# NRF24L01.net
KiCad netlist of a schematic drawn in Altium Designer
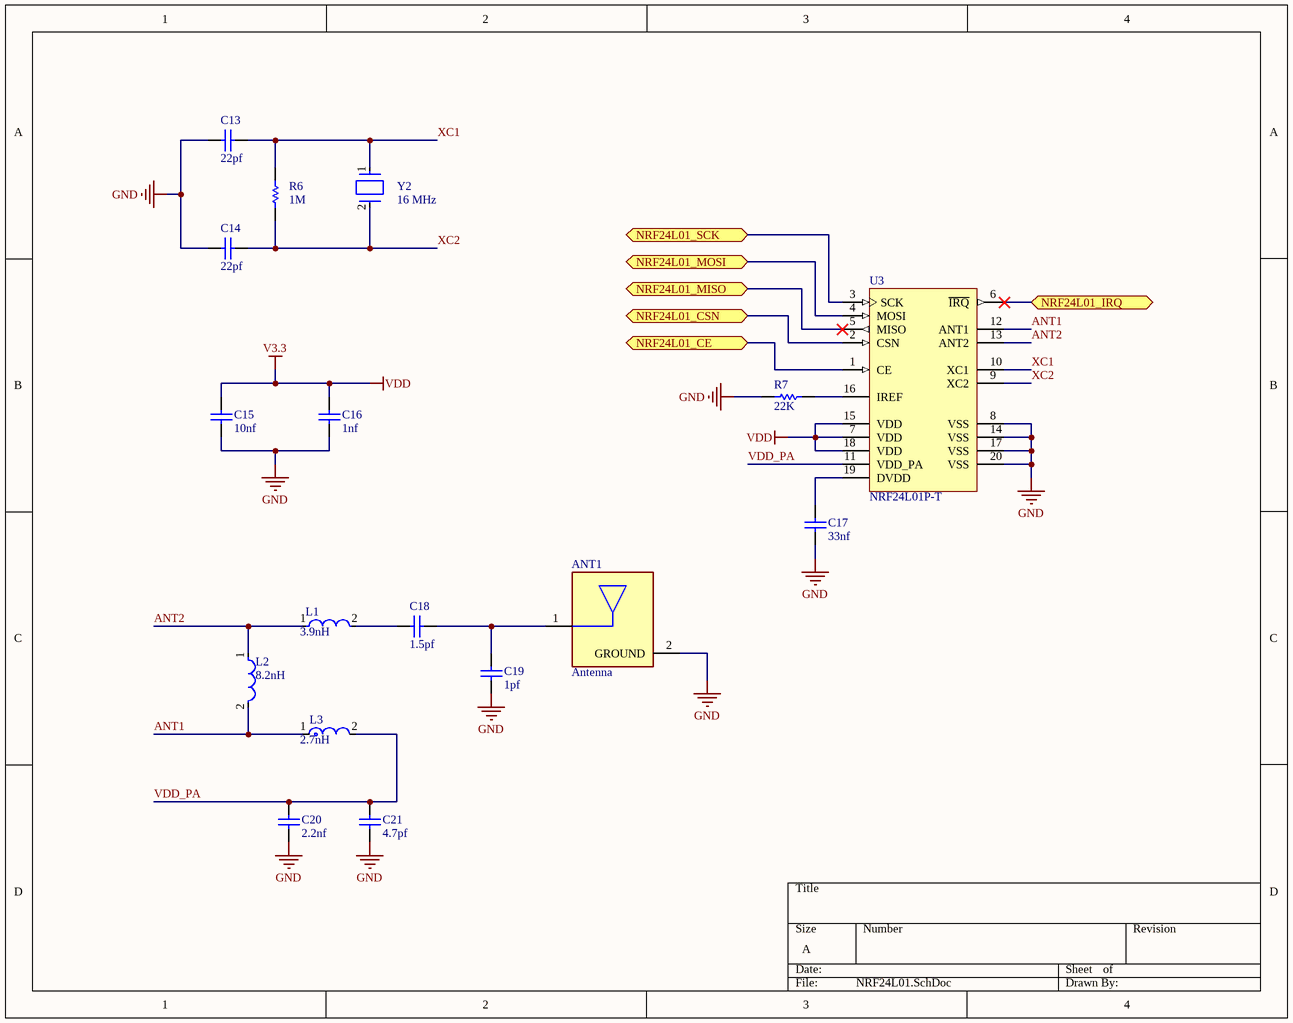
[diagram p0: NRF24L01.SchDoc]

(export (version "E")
  (design (tool "Eeschema 10.0.6"))
  (components
    (comp (ref "ANT1")
      (value "Antenna")
      (footprint "FP-211964-0001-MFG")
      (description "2.4/5GHZ LTCC ANT 3.2X1.6MM")
      (libsource (lib "Altium Content Vault") (part "8e307a9ba41921a4a20067ae005fd5e"))
    )
    (comp (ref "C13")
      (value "22pf")
      (footprint "CAPC1206(3216)190_N")
      (description "CAP 1206")
      (fields (field (name "TOLERANCE") "Â±10%"))
      (libsource (lib "Altium Content Vault") (part "CAP"))
    )
    (comp (ref "C14")
      (value "22pf")
      (footprint "CAPC1206(3216)190_N")
      (description "CAP 1206")
      (fields (field (name "TOLERANCE") "Â±10%"))
      (libsource (lib "Altium Content Vault") (part "CAP"))
    )
    (comp (ref "C15")
      (value "10nf")
      (footprint "CAPC1206(3216)190_N")
      (description "CAP 1206")
      (fields (field (name "TOLERANCE") "Â±10%"))
      (libsource (lib "Altium Content Vault") (part "CAP"))
    )
    (comp (ref "C16")
      (value "1nf")
      (footprint "CAPC1206(3216)190_N")
      (description "CAP 1206")
      (fields (field (name "TOLERANCE") "Â±10%"))
      (libsource (lib "Altium Content Vault") (part "CAP"))
    )
    (comp (ref "C17")
      (value "33nf")
      (footprint "CAPC1206(3216)190_N")
      (description "CAP 1206")
      (fields (field (name "TOLERANCE") "Â±10%"))
      (libsource (lib "Altium Content Vault") (part "CAP"))
    )
    (comp (ref "C18")
      (value "1.5pf")
      (footprint "CAPC1206(3216)190_N")
      (description "CAP 1206")
      (fields (field (name "TOLERANCE") "Â±10%"))
      (libsource (lib "Altium Content Vault") (part "CAP"))
    )
    (comp (ref "C19")
      (value "1pf")
      (footprint "CAPC1206(3216)190_N")
      (description "CAP 1206")
      (fields (field (name "TOLERANCE") "Â±10%"))
      (libsource (lib "Altium Content Vault") (part "CAP"))
    )
    (comp (ref "C20")
      (value "2.2nf")
      (footprint "CAPC1206(3216)190_N")
      (description "CAP 1206")
      (fields (field (name "TOLERANCE") "Â±10%"))
      (libsource (lib "Altium Content Vault") (part "CAP"))
    )
    (comp (ref "C21")
      (value "4.7pf")
      (footprint "CAPC1206(3216)190_N")
      (description "CAP 1206")
      (fields (field (name "TOLERANCE") "Â±10%"))
      (libsource (lib "Altium Content Vault") (part "CAP"))
    )
    (comp (ref "L1")
      (value "LQM21NNR15K10D")
      (footprint "FP-LQM21DN_00-IPC_B")
      (description "Multilayer Type Inductor for General Circuits, 0805 (2012), 0.15μH, 10%, 0.32Ω, 250mA")
      (fields (field (name "INDUCTANCE") "3.9nH") (field (name "TOLERANCE") "10%"))
      (libsource (lib "Altium Content Vault") (part "725321dda6339637d4d059423bc1c3c"))
    )
    (comp (ref "L2")
      (value "LQM21NNR15K10D")
      (footprint "FP-LQM21DN_00-IPC_B")
      (description "Multilayer Type Inductor for General Circuits, 0805 (2012), 0.15μH, 10%, 0.32Ω, 250mA")
      (fields (field (name "INDUCTANCE") "8.2nH") (field (name "TOLERANCE") "10%"))
      (libsource (lib "Altium Content Vault") (part "725321dda6339637d4d059423bc1c3c"))
    )
    (comp (ref "L3")
      (value "LQG18HN2N2S00D")
      (footprint "FP-LQG18HH_00-IPC_A")
      (description "Multilayer type RF Inductor 2.2nH ±0.3nH 0.1Ω 1100mA 0603")
      (fields (field (name "INDUCTANCE") "2.7nH"))
      (libsource (lib "Altium Content Vault") (part "4cc4b267dca4c8e51f7102f422741d8"))
    )
    (comp (ref "R6")
      (value "1M")
      (footprint "RESC3216X70X50NL05T20")
      (fields (field (name "MANUFACTURER") "Panasonic") (field (name "PART NUMBER") "ERJ-8GEY0R00V"))
      (libsource (lib "Altium Content Vault") (part "RES"))
    )
    (comp (ref "R7")
      (value "22K")
      (footprint "RESC3216X70X50NL05T20")
      (fields (field (name "MANUFACTURER") "Panasonic") (field (name "PART NUMBER") "ERJ-8GEY0R00V"))
      (libsource (lib "Altium Content Vault") (part "RES"))
    )
    (comp (ref "U3")
      (value "NRF24L01P-T")
      (footprint "NRSC-QFN-20_L")
      (description "Single Chip Transceiver, 2.4 GHz, 60 mW, 1.9 to 3.6 V, -40 to 85 degC, 20-Pin QFN, RoHS, Tray")
      (fields (field (name "MANUFACTURER") "Nordic Semiconductor"))
      (libsource (lib "Altium Content Vault") (part "NRSC-NRF24L01P-QFN-20"))
    )
    (comp (ref "Y2")
      (value "ABLS-8.000MHZ-B2-T")
      (footprint "FP-ABLS-MFG")
      (description "CRYSTAL 8.0000MHZ 18PF SMD")
      (fields (field (name "OPERATING FREQUENCY") "16 MHz") (field (name "TOLERANCE") "20ppm"))
      (libsource (lib "Altium Content Vault") (part "c23a69dc6c9e2f18f2079038eb95dd1"))
    )
  )
  (nets
    (net (code "1") (name "/ANT1") (class "Default")
      (node (ref "L2") (pin "2") (pinfunction "2_2") (pintype "passive"))
      (node (ref "L3") (pin "1") (pinfunction "1_1") (pintype "passive"))
      (node (ref "U3") (pin "12") (pinfunction "ANT1_12") (pintype "passive"))
    )
    (net (code "2") (name "/ANT2") (class "Default")
      (node (ref "L1") (pin "1") (pinfunction "1_1") (pintype "passive"))
      (node (ref "L2") (pin "1") (pinfunction "1_1") (pintype "passive"))
      (node (ref "U3") (pin "13") (pinfunction "ANT2_13") (pintype "passive"))
    )
    (net (code "3") (name "/NRF24L01_CE") (class "Default")
      (node (ref "U3") (pin "1") (pinfunction "CE_1") (pintype "input"))
    )
    (net (code "4") (name "/NRF24L01_CSN") (class "Default")
      (node (ref "U3") (pin "2") (pinfunction "CSN_2") (pintype "input"))
    )
    (net (code "5") (name "/NRF24L01_IRQ") (class "Default")
      (node (ref "U3") (pin "6") (pinfunction "~{IRQ}_6") (pintype "output+no_connect"))
    )
    (net (code "6") (name "/NRF24L01_MISO") (class "Default")
      (node (ref "U3") (pin "5") (pinfunction "MISO_5") (pintype "output+no_connect"))
    )
    (net (code "7") (name "/NRF24L01_MOSI") (class "Default")
      (node (ref "U3") (pin "4") (pinfunction "MOSI_4") (pintype "input"))
    )
    (net (code "8") (name "/NRF24L01_SCK") (class "Default")
      (node (ref "U3") (pin "3") (pinfunction "SCK_3") (pintype "input"))
    )
    (net (code "9") (name "/VDD_PA") (class "Default")
      (node (ref "C20") (pin "2") (pinfunction "2_2") (pintype "passive"))
      (node (ref "C21") (pin "2") (pinfunction "2_2") (pintype "passive"))
      (node (ref "L3") (pin "2") (pinfunction "2_2") (pintype "passive"))
      (node (ref "U3") (pin "11") (pinfunction "VDD_PA_11") (pintype "power_in"))
    )
    (net (code "10") (name "/XC1") (class "Default")
      (node (ref "C13") (pin "1") (pinfunction "1_1") (pintype "passive"))
      (node (ref "R6") (pin "2") (pinfunction "2_2") (pintype "passive"))
      (node (ref "U3") (pin "10") (pinfunction "XC1_10") (pintype "passive"))
      (node (ref "Y2") (pin "1") (pinfunction "1_1") (pintype "passive"))
    )
    (net (code "11") (name "/XC2") (class "Default")
      (node (ref "C14") (pin "1") (pinfunction "1_1") (pintype "passive"))
      (node (ref "R6") (pin "1") (pinfunction "1_1") (pintype "passive"))
      (node (ref "U3") (pin "9") (pinfunction "XC2_9") (pintype "passive"))
      (node (ref "Y2") (pin "2") (pinfunction "2_2") (pintype "passive"))
    )
    (net (code "12") (name "GND") (class "Default")
      (node (ref "ANT1") (pin "2") (pinfunction "GROUND_2") (pintype "power_in"))
      (node (ref "C13") (pin "2") (pinfunction "2_2") (pintype "passive"))
      (node (ref "C14") (pin "2") (pinfunction "2_2") (pintype "passive"))
      (node (ref "C15") (pin "2") (pinfunction "2_2") (pintype "passive"))
      (node (ref "C16") (pin "2") (pinfunction "2_2") (pintype "passive"))
      (node (ref "C17") (pin "2") (pinfunction "2_2") (pintype "passive"))
      (node (ref "C19") (pin "1") (pinfunction "1_1") (pintype "passive"))
      (node (ref "C20") (pin "1") (pinfunction "1_1") (pintype "passive"))
      (node (ref "C21") (pin "1") (pinfunction "1_1") (pintype "passive"))
      (node (ref "R7") (pin "2") (pinfunction "2_2") (pintype "passive"))
      (node (ref "U3") (pin "14") (pinfunction "VSS_14") (pintype "power_in"))
      (node (ref "U3") (pin "17") (pinfunction "VSS_17") (pintype "power_in"))
      (node (ref "U3") (pin "20") (pinfunction "VSS_20") (pintype "power_in"))
      (node (ref "U3") (pin "8") (pinfunction "VSS_8") (pintype "power_in"))
    )
    (net (code "13") (name "Net-(ANT1-FEED)") (class "Default")
      (node (ref "ANT1") (pin "1") (pinfunction "FEED_1") (pintype "passive"))
      (node (ref "C18") (pin "2") (pinfunction "2_2") (pintype "passive"))
      (node (ref "C19") (pin "2") (pinfunction "2_2") (pintype "passive"))
    )
    (net (code "14") (name "Net-(C18-Pad1)") (class "Default")
      (node (ref "C18") (pin "1") (pinfunction "1_1") (pintype "passive"))
      (node (ref "L1") (pin "2") (pinfunction "2_2") (pintype "passive"))
    )
    (net (code "15") (name "Net-(U3-DVDD)") (class "Default")
      (node (ref "C17") (pin "1") (pinfunction "1_1") (pintype "passive"))
      (node (ref "U3") (pin "19") (pinfunction "DVDD_19") (pintype "power_in"))
    )
    (net (code "16") (name "Net-(U3-IREF)") (class "Default")
      (node (ref "R7") (pin "1") (pinfunction "1_1") (pintype "passive"))
      (node (ref "U3") (pin "16") (pinfunction "IREF_16") (pintype "passive"))
    )
    (net (code "17") (name "V3.3") (class "Default")
      (node (ref "C15") (pin "1") (pinfunction "1_1") (pintype "passive"))
      (node (ref "C16") (pin "1") (pinfunction "1_1") (pintype "passive"))
      (node (ref "U3") (pin "15") (pinfunction "VDD_15") (pintype "power_in"))
      (node (ref "U3") (pin "18") (pinfunction "VDD_18") (pintype "power_in"))
      (node (ref "U3") (pin "7") (pinfunction "VDD_7") (pintype "power_in"))
    )
  )
)
